# controller.net
KiCad netlist of a schematic drawn in EAGLE
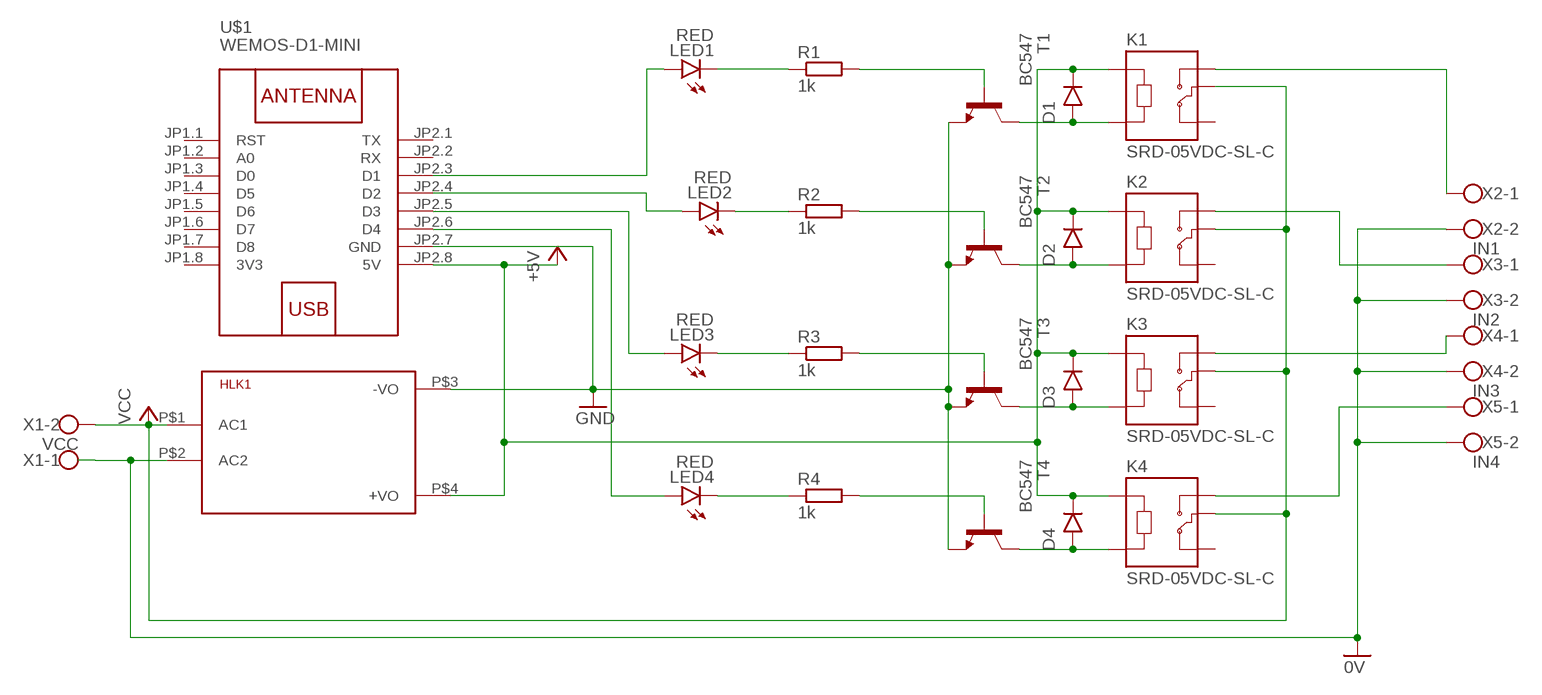
[diagram p0: schematic, sheet 1]

(export (version "E")
  (design (tool "Eeschema 10.0.6"))
  (components
    (comp (ref "D1")
      (value "1N4001")
      (footprint "eagle-import:DO41-10")
      (libsource (lib "eagle-import") (part "1N4001"))
    )
    (comp (ref "D2")
      (value "1N4001")
      (footprint "eagle-import:DO41-10")
      (libsource (lib "eagle-import") (part "1N4001"))
    )
    (comp (ref "D3")
      (value "1N4001")
      (footprint "eagle-import:DO41-10")
      (libsource (lib "eagle-import") (part "1N4001"))
    )
    (comp (ref "D4")
      (value "1N4001")
      (footprint "eagle-import:DO41-10")
      (libsource (lib "eagle-import") (part "1N4001"))
    )
    (comp (ref "HLK1")
      (value "HLK-PM013W")
      (footprint "eagle-import:HLK-PM01")
      (libsource (lib "eagle-import") (part "HLK-PM013W"))
    )
    (comp (ref "K1")
      (value "SRD-05VDC-SL-C")
      (footprint "eagle-import:RELAY_SRD-05VDC-SL-C")
      (fields (field (name "MF") "Songle Relay"))
      (libsource (lib "eagle-import") (part "SRD-05VDC-SL-C"))
    )
    (comp (ref "K2")
      (value "SRD-05VDC-SL-C")
      (footprint "eagle-import:RELAY_SRD-05VDC-SL-C")
      (fields (field (name "MF") "Songle Relay"))
      (libsource (lib "eagle-import") (part "SRD-05VDC-SL-C"))
    )
    (comp (ref "K3")
      (value "SRD-05VDC-SL-C")
      (footprint "eagle-import:RELAY_SRD-05VDC-SL-C")
      (fields (field (name "MF") "Songle Relay"))
      (libsource (lib "eagle-import") (part "SRD-05VDC-SL-C"))
    )
    (comp (ref "K4")
      (value "SRD-05VDC-SL-C")
      (footprint "eagle-import:RELAY_SRD-05VDC-SL-C")
      (fields (field (name "MF") "Songle Relay"))
      (libsource (lib "eagle-import") (part "SRD-05VDC-SL-C"))
    )
    (comp (ref "LED1")
      (value "RED")
      (footprint "eagle-import:LED3MM")
      (libsource (lib "eagle-import") (part "LED3MM"))
    )
    (comp (ref "LED2")
      (value "RED")
      (footprint "eagle-import:LED3MM")
      (libsource (lib "eagle-import") (part "LED3MM"))
    )
    (comp (ref "LED3")
      (value "RED")
      (footprint "eagle-import:LED3MM")
      (libsource (lib "eagle-import") (part "LED3MM"))
    )
    (comp (ref "LED4")
      (value "RED")
      (footprint "eagle-import:LED3MM")
      (libsource (lib "eagle-import") (part "LED3MM"))
    )
    (comp (ref "R1")
      (value "1k")
      (footprint "eagle-import:0204_5")
      (libsource (lib "eagle-import") (part "R-EU_0204/5"))
    )
    (comp (ref "R2")
      (value "1k")
      (footprint "eagle-import:0204_5")
      (libsource (lib "eagle-import") (part "R-EU_0204/5"))
    )
    (comp (ref "R3")
      (value "1k")
      (footprint "eagle-import:0204_5")
      (libsource (lib "eagle-import") (part "R-EU_0204/5"))
    )
    (comp (ref "R4")
      (value "1k")
      (footprint "eagle-import:0204_5")
      (libsource (lib "eagle-import") (part "R-EU_0204/5"))
    )
    (comp (ref "T1")
      (value "BC547")
      (footprint "eagle-import:TO92")
      (libsource (lib "eagle-import") (part "BC547"))
    )
    (comp (ref "T2")
      (value "BC547")
      (footprint "eagle-import:TO92")
      (libsource (lib "eagle-import") (part "BC547"))
    )
    (comp (ref "T3")
      (value "BC547")
      (footprint "eagle-import:TO92")
      (libsource (lib "eagle-import") (part "BC547"))
    )
    (comp (ref "T4")
      (value "BC547")
      (footprint "eagle-import:TO92")
      (libsource (lib "eagle-import") (part "BC547"))
    )
    (comp (ref "U$1")
      (value "WEMOS-D1-MINI")
      (footprint "eagle-import:WEMOS-D1-MINI")
      (libsource (lib "eagle-import") (part "WEMOS-D1-MINI"))
    )
    (comp (ref "X1")
      (value "VCC")
      (footprint "eagle-import:W237-102")
      (fields (field (name "MPN") "237-102"))
      (libsource (lib "eagle-import") (part "W237-102"))
    )
    (comp (ref "X2")
      (value "IN1")
      (footprint "eagle-import:W237-102")
      (fields (field (name "MPN") "237-102"))
      (libsource (lib "eagle-import") (part "W237-102"))
    )
    (comp (ref "X3")
      (value "IN2")
      (footprint "eagle-import:W237-102")
      (fields (field (name "MPN") "237-102"))
      (libsource (lib "eagle-import") (part "W237-102"))
    )
    (comp (ref "X4")
      (value "IN3")
      (footprint "eagle-import:W237-102")
      (fields (field (name "MPN") "237-102"))
      (libsource (lib "eagle-import") (part "W237-102"))
    )
    (comp (ref "X5")
      (value "IN4")
      (footprint "eagle-import:W237-102")
      (fields (field (name "MPN") "237-102"))
      (libsource (lib "eagle-import") (part "W237-102"))
    )
  )
  (nets
    (net (code "1") (name "+5V") (class "Default")
      (node (ref "D1") (pin "C") (pinfunction "CATHODE_C") (pintype "passive"))
      (node (ref "D2") (pin "C") (pinfunction "CATHODE_C") (pintype "passive"))
      (node (ref "D3") (pin "C") (pinfunction "CATHODE_C") (pintype "passive"))
      (node (ref "D4") (pin "C") (pinfunction "CATHODE_C") (pintype "passive"))
      (node (ref "HLK1") (pin "P$4") (pinfunction "+VO_P$4") (pintype "bidirectional"))
      (node (ref "K1") (pin "A1") (pinfunction "A1_A1") (pintype "passive"))
      (node (ref "K2") (pin "A1") (pinfunction "A1_A1") (pintype "passive"))
      (node (ref "K3") (pin "A1") (pinfunction "A1_A1") (pintype "passive"))
      (node (ref "K4") (pin "A1") (pinfunction "A1_A1") (pintype "passive"))
      (node (ref "U$1") (pin "JP2.8") (pinfunction "5V_JP2.8") (pintype "power_in"))
    )
    (net (code "2") (name "/3V3") (class "Default")
      (node (ref "U$1") (pin "JP1.8") (pinfunction "3V3_JP1.8") (pintype "power_in"))
    )
    (net (code "3") (name "0V") (class "Default")
      (node (ref "HLK1") (pin "P$2") (pinfunction "AC2_P$2") (pintype "bidirectional"))
      (node (ref "X1") (pin "1") (pinfunction "KL_1") (pintype "passive"))
      (node (ref "X2") (pin "2") (pinfunction "KL_2") (pintype "passive"))
      (node (ref "X3") (pin "2") (pinfunction "KL_2") (pintype "passive"))
      (node (ref "X4") (pin "2") (pinfunction "KL_2") (pintype "passive"))
      (node (ref "X5") (pin "2") (pinfunction "KL_2") (pintype "passive"))
    )
    (net (code "4") (name "GND") (class "Default")
      (node (ref "HLK1") (pin "P$3") (pinfunction "-VO_P$3") (pintype "bidirectional"))
      (node (ref "T1") (pin "1") (pinfunction "E_1") (pintype "passive"))
      (node (ref "T2") (pin "1") (pinfunction "E_1") (pintype "passive"))
      (node (ref "T3") (pin "1") (pinfunction "E_1") (pintype "passive"))
      (node (ref "T4") (pin "1") (pinfunction "E_1") (pintype "passive"))
      (node (ref "U$1") (pin "JP2.7") (pinfunction "GND_JP2.7") (pintype "power_in"))
    )
    (net (code "5") (name "Net-(D1-ANODE)") (class "Default")
      (node (ref "D1") (pin "A") (pinfunction "ANODE_A") (pintype "passive"))
      (node (ref "K1") (pin "A2") (pinfunction "A2_A2") (pintype "passive"))
      (node (ref "T1") (pin "3") (pinfunction "C_3") (pintype "passive"))
    )
    (net (code "6") (name "Net-(D2-ANODE)") (class "Default")
      (node (ref "D2") (pin "A") (pinfunction "ANODE_A") (pintype "passive"))
      (node (ref "K2") (pin "A2") (pinfunction "A2_A2") (pintype "passive"))
      (node (ref "T2") (pin "3") (pinfunction "C_3") (pintype "passive"))
    )
    (net (code "7") (name "Net-(D3-ANODE)") (class "Default")
      (node (ref "D3") (pin "A") (pinfunction "ANODE_A") (pintype "passive"))
      (node (ref "K3") (pin "A2") (pinfunction "A2_A2") (pintype "passive"))
      (node (ref "T3") (pin "3") (pinfunction "C_3") (pintype "passive"))
    )
    (net (code "8") (name "Net-(D4-ANODE)") (class "Default")
      (node (ref "D4") (pin "A") (pinfunction "ANODE_A") (pintype "passive"))
      (node (ref "K4") (pin "A2") (pinfunction "A2_A2") (pintype "passive"))
      (node (ref "T4") (pin "3") (pinfunction "C_3") (pintype "passive"))
    )
    (net (code "9") (name "Net-(LED1-C)") (class "Default")
      (node (ref "LED1") (pin "K") (pinfunction "C_K") (pintype "passive"))
      (node (ref "R1") (pin "1") (pinfunction "1_1") (pintype "passive"))
    )
    (net (code "10") (name "Net-(LED2-C)") (class "Default")
      (node (ref "LED2") (pin "K") (pinfunction "C_K") (pintype "passive"))
      (node (ref "R2") (pin "1") (pinfunction "1_1") (pintype "passive"))
    )
    (net (code "11") (name "Net-(LED3-C)") (class "Default")
      (node (ref "LED3") (pin "K") (pinfunction "C_K") (pintype "passive"))
      (node (ref "R3") (pin "1") (pinfunction "1_1") (pintype "passive"))
    )
    (net (code "12") (name "Net-(LED4-C)") (class "Default")
      (node (ref "LED4") (pin "K") (pinfunction "C_K") (pintype "passive"))
      (node (ref "R4") (pin "1") (pinfunction "1_1") (pintype "passive"))
    )
    (net (code "13") (name "Net-(T1-B)") (class "Default")
      (node (ref "R1") (pin "2") (pinfunction "2_2") (pintype "passive"))
      (node (ref "T1") (pin "2") (pinfunction "B_2") (pintype "passive"))
    )
    (net (code "14") (name "Net-(T2-B)") (class "Default")
      (node (ref "R2") (pin "2") (pinfunction "2_2") (pintype "passive"))
      (node (ref "T2") (pin "2") (pinfunction "B_2") (pintype "passive"))
    )
    (net (code "15") (name "Net-(T3-B)") (class "Default")
      (node (ref "R3") (pin "2") (pinfunction "2_2") (pintype "passive"))
      (node (ref "T3") (pin "2") (pinfunction "B_2") (pintype "passive"))
    )
    (net (code "16") (name "Net-(T4-B)") (class "Default")
      (node (ref "R4") (pin "2") (pinfunction "2_2") (pintype "passive"))
      (node (ref "T4") (pin "2") (pinfunction "B_2") (pintype "passive"))
    )
    (net (code "17") (name "Net-(U$1-D1)") (class "Default")
      (node (ref "LED1") (pin "A") (pinfunction "A_A") (pintype "passive"))
      (node (ref "U$1") (pin "JP2.3") (pinfunction "D1_JP2.3") (pintype "bidirectional"))
    )
    (net (code "18") (name "Net-(U$1-D2)") (class "Default")
      (node (ref "LED2") (pin "A") (pinfunction "A_A") (pintype "passive"))
      (node (ref "U$1") (pin "JP2.4") (pinfunction "D2_JP2.4") (pintype "bidirectional"))
    )
    (net (code "19") (name "Net-(U$1-D3)") (class "Default")
      (node (ref "LED3") (pin "A") (pinfunction "A_A") (pintype "passive"))
      (node (ref "U$1") (pin "JP2.5") (pinfunction "D3_JP2.5") (pintype "bidirectional"))
    )
    (net (code "20") (name "Net-(U$1-D4)") (class "Default")
      (node (ref "LED4") (pin "A") (pinfunction "A_A") (pintype "passive"))
      (node (ref "U$1") (pin "JP2.6") (pinfunction "D4_JP2.6") (pintype "bidirectional"))
    )
    (net (code "21") (name "Net-(X2A-KL)") (class "Default")
      (node (ref "K1") (pin "NO") (pinfunction "NO_NO") (pintype "passive"))
      (node (ref "X2") (pin "1") (pinfunction "KL_1") (pintype "passive"))
    )
    (net (code "22") (name "Net-(X3A-KL)") (class "Default")
      (node (ref "K2") (pin "NO") (pinfunction "NO_NO") (pintype "passive"))
      (node (ref "X3") (pin "1") (pinfunction "KL_1") (pintype "passive"))
    )
    (net (code "23") (name "Net-(X4A-KL)") (class "Default")
      (node (ref "K3") (pin "NO") (pinfunction "NO_NO") (pintype "passive"))
      (node (ref "X4") (pin "1") (pinfunction "KL_1") (pintype "passive"))
    )
    (net (code "24") (name "Net-(X5A-KL)") (class "Default")
      (node (ref "K4") (pin "NO") (pinfunction "NO_NO") (pintype "passive"))
      (node (ref "X5") (pin "1") (pinfunction "KL_1") (pintype "passive"))
    )
    (net (code "25") (name "VCC") (class "Default")
      (node (ref "HLK1") (pin "P$1") (pinfunction "AC1_P$1") (pintype "bidirectional"))
      (node (ref "K1") (pin "COM") (pinfunction "COM_COM") (pintype "passive"))
      (node (ref "K2") (pin "COM") (pinfunction "COM_COM") (pintype "passive"))
      (node (ref "K3") (pin "COM") (pinfunction "COM_COM") (pintype "passive"))
      (node (ref "K4") (pin "COM") (pinfunction "COM_COM") (pintype "passive"))
      (node (ref "X1") (pin "2") (pinfunction "KL_2") (pintype "passive"))
    )
    (net (code "26") (name "unconnected-(K1-PadNC)") (class "Default")
      (node (ref "K1") (pin "NC") (pinfunction "NC_NC") (pintype "passive"))
    )
    (net (code "27") (name "unconnected-(K2-PadNC)") (class "Default")
      (node (ref "K2") (pin "NC") (pinfunction "NC_NC") (pintype "passive"))
    )
    (net (code "28") (name "unconnected-(K3-PadNC)") (class "Default")
      (node (ref "K3") (pin "NC") (pinfunction "NC_NC") (pintype "passive"))
    )
    (net (code "29") (name "unconnected-(K4-PadNC)") (class "Default")
      (node (ref "K4") (pin "NC") (pinfunction "NC_NC") (pintype "passive"))
    )
    (net (code "30") (name "unconnected-(U$1-A0-PadJP1.2)") (class "Default")
      (node (ref "U$1") (pin "JP1.2") (pinfunction "A0_JP1.2") (pintype "bidirectional"))
    )
    (net (code "31") (name "unconnected-(U$1-D0-PadJP1.3)") (class "Default")
      (node (ref "U$1") (pin "JP1.3") (pinfunction "D0_JP1.3") (pintype "bidirectional"))
    )
    (net (code "32") (name "unconnected-(U$1-D5-PadJP1.4)") (class "Default")
      (node (ref "U$1") (pin "JP1.4") (pinfunction "D5_JP1.4") (pintype "bidirectional"))
    )
    (net (code "33") (name "unconnected-(U$1-D6-PadJP1.5)") (class "Default")
      (node (ref "U$1") (pin "JP1.5") (pinfunction "D6_JP1.5") (pintype "bidirectional"))
    )
    (net (code "34") (name "unconnected-(U$1-D7-PadJP1.6)") (class "Default")
      (node (ref "U$1") (pin "JP1.6") (pinfunction "D7_JP1.6") (pintype "bidirectional"))
    )
    (net (code "35") (name "unconnected-(U$1-D8-PadJP1.7)") (class "Default")
      (node (ref "U$1") (pin "JP1.7") (pinfunction "D8_JP1.7") (pintype "bidirectional"))
    )
    (net (code "36") (name "unconnected-(U$1-RST-PadJP1.1)") (class "Default")
      (node (ref "U$1") (pin "JP1.1") (pinfunction "RST_JP1.1") (pintype "bidirectional"))
    )
    (net (code "37") (name "unconnected-(U$1-RX-PadJP2.2)") (class "Default")
      (node (ref "U$1") (pin "JP2.2") (pinfunction "RX_JP2.2") (pintype "bidirectional"))
    )
    (net (code "38") (name "unconnected-(U$1-TX-PadJP2.1)") (class "Default")
      (node (ref "U$1") (pin "JP2.1") (pinfunction "TX_JP2.1") (pintype "bidirectional"))
    )
  )
)
